# MXP_part.net
KiCad netlist of a schematic drawn in EAGLE
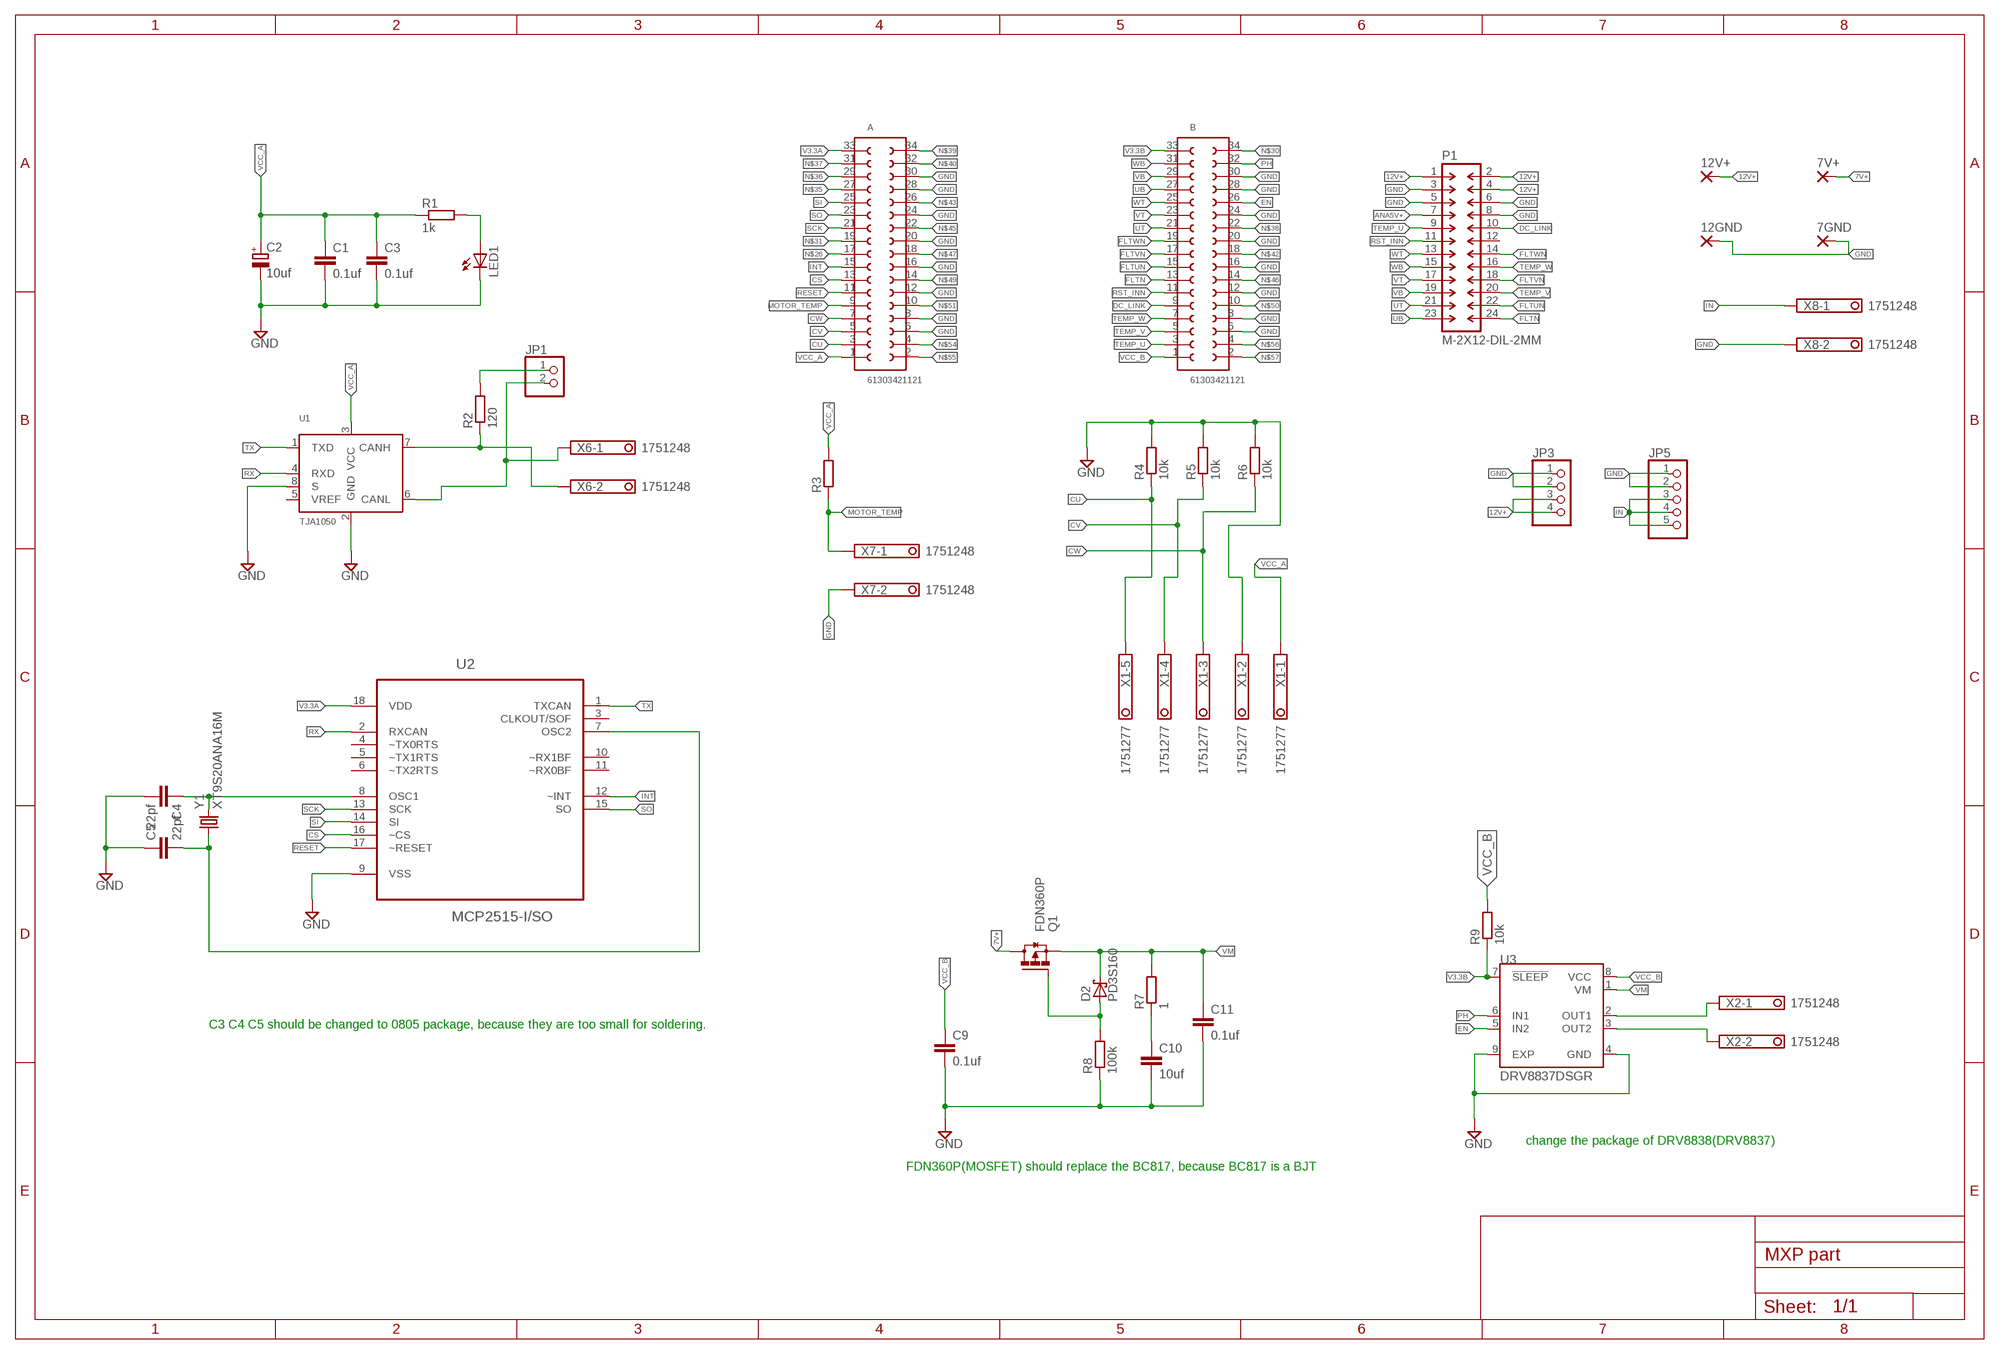
[diagram p0: schematic, sheet 1]

(export (version "E")
  (design (tool "Eeschema 10.0.6"))
  (components
    (comp (ref "7GND")
      (value "2,54/0,9")
      (footprint "eagle-import:2,54_0,9")
      (libsource (lib "eagle-import") (part "2,54/0,9"))
    )
    (comp (ref "7V+")
      (value "2,54/0,9")
      (footprint "eagle-import:2,54_0,9")
      (libsource (lib "eagle-import") (part "2,54/0,9"))
    )
    (comp (ref "12GND")
      (value "2,54/0,9")
      (footprint "eagle-import:2,54_0,9")
      (libsource (lib "eagle-import") (part "2,54/0,9"))
    )
    (comp (ref "12V+")
      (value "2,54/0,9")
      (footprint "eagle-import:2,54_0,9")
      (libsource (lib "eagle-import") (part "2,54/0,9"))
    )
    (comp (ref "A")
      (value "61303421121")
      (footprint "eagle-import:61303421121")
      (fields (field (name "MF") "Würth Elektronik"))
      (libsource (lib "eagle-import") (part "61303421121"))
    )
    (comp (ref "B")
      (value "61303421121")
      (footprint "eagle-import:61303421121")
      (fields (field (name "MF") "Würth Elektronik"))
      (libsource (lib "eagle-import") (part "61303421121"))
    )
    (comp (ref "C1")
      (value "0.1uf")
      (footprint "eagle-import:C0402K")
      (libsource (lib "eagle-import") (part "C-EUC0402K"))
    )
    (comp (ref "C2")
      (value "10uf")
      (footprint "eagle-import:A_3216-18W")
      (libsource (lib "eagle-import") (part "CPOL-EUA/3216-18W"))
    )
    (comp (ref "C3")
      (value "0.1uf")
      (footprint "eagle-import:C0402K")
      (libsource (lib "eagle-import") (part "C-EUC0402K"))
    )
    (comp (ref "C4")
      (value "22pf")
      (footprint "eagle-import:C0402K")
      (libsource (lib "eagle-import") (part "C-EUC0402K"))
    )
    (comp (ref "C5")
      (value "22pf")
      (footprint "eagle-import:C0402K")
      (libsource (lib "eagle-import") (part "C-EUC0402K"))
    )
    (comp (ref "C9")
      (value "0.1uf")
      (footprint "eagle-import:C0603K")
      (libsource (lib "eagle-import") (part "C-EUC0603K"))
    )
    (comp (ref "C10")
      (value "10uf")
      (footprint "eagle-import:C0603K")
      (libsource (lib "eagle-import") (part "C-EUC0603K"))
    )
    (comp (ref "C11")
      (value "0.1uf")
      (footprint "eagle-import:C0603K")
      (libsource (lib "eagle-import") (part "C-EUC0603K"))
    )
    (comp (ref "D2")
      (value "PD3S160")
      (footprint "eagle-import:POWERDI323")
      (libsource (lib "eagle-import") (part "PD3S160"))
    )
    (comp (ref "JP1")
      (value "PINHD-1X2")
      (footprint "eagle-import:1X02")
      (libsource (lib "eagle-import") (part "PINHD-1X2"))
    )
    (comp (ref "JP3")
      (value "PINHD-1X4")
      (footprint "eagle-import:1X04")
      (libsource (lib "eagle-import") (part "PINHD-1X4"))
    )
    (comp (ref "JP5")
      (value "PINHD-1X5")
      (footprint "eagle-import:1X05")
      (libsource (lib "eagle-import") (part "PINHD-1X5"))
    )
    (comp (ref "LED1")
      (value "LEDCHIP-LED0805")
      (footprint "eagle-import:CHIP-LED0805")
      (libsource (lib "eagle-import") (part "LEDCHIP-LED0805"))
    )
    (comp (ref "P1")
      (value "M-2X12-DIL-2MM")
      (footprint "eagle-import:DIL-2MM-2X12")
      (libsource (lib "eagle-import") (part "M-2X12-DIL-2MM"))
    )
    (comp (ref "Q1")
      (value "FDN360P")
      (footprint "eagle-import:SUPER-SOT3")
      (libsource (lib "eagle-import") (part "FDN360P"))
    )
    (comp (ref "R1")
      (value "1k")
      (footprint "eagle-import:R0603")
      (libsource (lib "eagle-import") (part "R-EU_R0603"))
    )
    (comp (ref "R2")
      (value "120")
      (footprint "eagle-import:R0603")
      (libsource (lib "eagle-import") (part "R-EU_R0603"))
    )
    (comp (ref "R3")
      (value "R-EU_0204/7")
      (footprint "eagle-import:0204_7")
      (libsource (lib "eagle-import") (part "R-EU_0204/7"))
    )
    (comp (ref "R4")
      (value "10k")
      (footprint "eagle-import:0204_7")
      (libsource (lib "eagle-import") (part "R-EU_0204/7"))
    )
    (comp (ref "R5")
      (value "10k")
      (footprint "eagle-import:0204_7")
      (libsource (lib "eagle-import") (part "R-EU_0204/7"))
    )
    (comp (ref "R6")
      (value "10k")
      (footprint "eagle-import:0204_7")
      (libsource (lib "eagle-import") (part "R-EU_0204/7"))
    )
    (comp (ref "R7")
      (value "1")
      (footprint "eagle-import:R0603")
      (libsource (lib "eagle-import") (part "R-EU_R0603"))
    )
    (comp (ref "R8")
      (value "100k")
      (footprint "eagle-import:R0603")
      (libsource (lib "eagle-import") (part "R-EU_R0603"))
    )
    (comp (ref "R9")
      (value "10k")
      (footprint "eagle-import:R0603")
      (libsource (lib "eagle-import") (part "R-EU_R0603"))
    )
    (comp (ref "U1")
      (value "TJA1050")
      (footprint "eagle-import:SOT96-1")
      (libsource (lib "eagle-import") (part "TJA1050"))
    )
    (comp (ref "U2")
      (value "MCP2515-I/SO")
      (footprint "eagle-import:SOIC127P1034X264-18N")
      (fields (field (name "MF") "Microchip"))
      (libsource (lib "eagle-import") (part "MCP2515-I/SO"))
    )
    (comp (ref "U3")
      (value "DRV8837DSGR")
      (footprint "eagle-import:SON50P200X200X80-9N")
      (fields (field (name "MF") "Texas Instruments"))
      (libsource (lib "eagle-import") (part "DRV8837DSGR"))
    )
    (comp (ref "X1")
      (value "1751277")
      (footprint "eagle-import:1751277")
      (libsource (lib "eagle-import") (part "1751277"))
    )
    (comp (ref "X2")
      (value "1751248")
      (footprint "eagle-import:1751248")
      (libsource (lib "eagle-import") (part "1751248"))
    )
    (comp (ref "X6")
      (value "1751248")
      (footprint "eagle-import:1751248")
      (libsource (lib "eagle-import") (part "1751248"))
    )
    (comp (ref "X7")
      (value "1751248")
      (footprint "eagle-import:1751248")
      (libsource (lib "eagle-import") (part "1751248"))
    )
    (comp (ref "X8")
      (value "1751248")
      (footprint "eagle-import:1751248")
      (libsource (lib "eagle-import") (part "1751248"))
    )
    (comp (ref "Y1")
      (value "XT9S20ANA16M")
      (footprint "eagle-import:XTAL_XT9S20ANA16M")
      (fields (field (name "MF") "Vishay Dale"))
      (libsource (lib "eagle-import") (part "XT9S20ANA16M"))
    )
  )
  (nets
    (net (code "1") (name "7V+") (class "Default")
      (node (ref "7V+") (pin "1") (pinfunction "P_1") (pintype "passive"))
      (node (ref "Q1") (pin "3") (pinfunction "D_3") (pintype "passive"))
    )
    (net (code "2") (name "12V+") (class "Default")
      (node (ref "12V+") (pin "1") (pinfunction "P_1") (pintype "passive"))
      (node (ref "JP3") (pin "3") (pinfunction "3_3") (pintype "passive"))
      (node (ref "JP3") (pin "4") (pinfunction "4_4") (pintype "passive"))
      (node (ref "P1") (pin "1") (pinfunction "1_1") (pintype "passive"))
      (node (ref "P1") (pin "2") (pinfunction "2_2") (pintype "passive"))
      (node (ref "P1") (pin "4") (pinfunction "4_4") (pintype "passive"))
    )
    (net (code "3") (name "ANA5V+") (class "Default")
      (node (ref "P1") (pin "7") (pinfunction "7_7") (pintype "passive"))
    )
    (net (code "4") (name "CS") (class "Default")
      (node (ref "A") (pin "13") (pinfunction "13_13") (pintype "passive"))
      (node (ref "U2") (pin "16") (pinfunction "~{CS}_16") (pintype "input"))
    )
    (net (code "5") (name "CU") (class "Default")
      (node (ref "A") (pin "3") (pinfunction "3_3") (pintype "passive"))
      (node (ref "R4") (pin "1") (pinfunction "1_1") (pintype "passive"))
      (node (ref "X1") (pin "5") (pinfunction "K_5") (pintype "passive"))
    )
    (net (code "6") (name "CV") (class "Default")
      (node (ref "A") (pin "5") (pinfunction "5_5") (pintype "passive"))
      (node (ref "R5") (pin "1") (pinfunction "1_1") (pintype "passive"))
      (node (ref "X1") (pin "4") (pinfunction "K_4") (pintype "passive"))
    )
    (net (code "7") (name "CW") (class "Default")
      (node (ref "A") (pin "7") (pinfunction "7_7") (pintype "passive"))
      (node (ref "R6") (pin "1") (pinfunction "1_1") (pintype "passive"))
      (node (ref "X1") (pin "3") (pinfunction "K_3") (pintype "passive"))
    )
    (net (code "8") (name "DC_LINK") (class "Default")
      (node (ref "B") (pin "9") (pinfunction "9_9") (pintype "passive"))
      (node (ref "P1") (pin "10") (pinfunction "10_10") (pintype "passive"))
    )
    (net (code "9") (name "EN") (class "Default")
      (node (ref "B") (pin "26") (pinfunction "26_26") (pintype "passive"))
      (node (ref "U3") (pin "5") (pinfunction "IN2_5") (pintype "input"))
    )
    (net (code "10") (name "FLTN") (class "Default")
      (node (ref "B") (pin "13") (pinfunction "13_13") (pintype "passive"))
      (node (ref "P1") (pin "24") (pinfunction "24_24") (pintype "passive"))
    )
    (net (code "11") (name "FLTUN") (class "Default")
      (node (ref "B") (pin "15") (pinfunction "15_15") (pintype "passive"))
      (node (ref "P1") (pin "22") (pinfunction "22_22") (pintype "passive"))
    )
    (net (code "12") (name "FLTVN") (class "Default")
      (node (ref "B") (pin "17") (pinfunction "17_17") (pintype "passive"))
      (node (ref "P1") (pin "18") (pinfunction "18_18") (pintype "passive"))
    )
    (net (code "13") (name "FLTWN") (class "Default")
      (node (ref "B") (pin "19") (pinfunction "19_19") (pintype "passive"))
      (node (ref "P1") (pin "14") (pinfunction "14_14") (pintype "passive"))
    )
    (net (code "14") (name "GND") (class "Default")
      (node (ref "12GND") (pin "1") (pinfunction "P_1") (pintype "passive"))
      (node (ref "7GND") (pin "1") (pinfunction "P_1") (pintype "passive"))
      (node (ref "A") (pin "12") (pinfunction "12_12") (pintype "passive"))
      (node (ref "A") (pin "16") (pinfunction "16_16") (pintype "passive"))
      (node (ref "A") (pin "20") (pinfunction "20_20") (pintype "passive"))
      (node (ref "A") (pin "24") (pinfunction "24_24") (pintype "passive"))
      (node (ref "A") (pin "28") (pinfunction "28_28") (pintype "passive"))
      (node (ref "A") (pin "30") (pinfunction "30_30") (pintype "passive"))
      (node (ref "A") (pin "6") (pinfunction "6_6") (pintype "passive"))
      (node (ref "A") (pin "8") (pinfunction "8_8") (pintype "passive"))
      (node (ref "B") (pin "12") (pinfunction "12_12") (pintype "passive"))
      (node (ref "B") (pin "16") (pinfunction "16_16") (pintype "passive"))
      (node (ref "B") (pin "20") (pinfunction "20_20") (pintype "passive"))
      (node (ref "B") (pin "24") (pinfunction "24_24") (pintype "passive"))
      (node (ref "B") (pin "28") (pinfunction "28_28") (pintype "passive"))
      (node (ref "B") (pin "30") (pinfunction "30_30") (pintype "passive"))
      (node (ref "B") (pin "6") (pinfunction "6_6") (pintype "passive"))
      (node (ref "B") (pin "8") (pinfunction "8_8") (pintype "passive"))
      (node (ref "C1") (pin "2") (pinfunction "2_2") (pintype "passive"))
      (node (ref "C10") (pin "2") (pinfunction "2_2") (pintype "passive"))
      (node (ref "C11") (pin "2") (pinfunction "2_2") (pintype "passive"))
      (node (ref "C2") (pin "-") (pinfunction "-_-") (pintype "passive"))
      (node (ref "C3") (pin "2") (pinfunction "2_2") (pintype "passive"))
      (node (ref "C4") (pin "2") (pinfunction "2_2") (pintype "passive"))
      (node (ref "C5") (pin "1") (pinfunction "1_1") (pintype "passive"))
      (node (ref "C9") (pin "2") (pinfunction "2_2") (pintype "passive"))
      (node (ref "JP3") (pin "1") (pinfunction "1_1") (pintype "passive"))
      (node (ref "JP3") (pin "2") (pinfunction "2_2") (pintype "passive"))
      (node (ref "JP5") (pin "1") (pinfunction "1_1") (pintype "passive"))
      (node (ref "JP5") (pin "2") (pinfunction "2_2") (pintype "passive"))
      (node (ref "LED1") (pin "C") (pinfunction "C_C") (pintype "passive"))
      (node (ref "P1") (pin "3") (pinfunction "3_3") (pintype "passive"))
      (node (ref "P1") (pin "5") (pinfunction "5_5") (pintype "passive"))
      (node (ref "P1") (pin "6") (pinfunction "6_6") (pintype "passive"))
      (node (ref "P1") (pin "8") (pinfunction "8_8") (pintype "passive"))
      (node (ref "R4") (pin "2") (pinfunction "2_2") (pintype "passive"))
      (node (ref "R5") (pin "2") (pinfunction "2_2") (pintype "passive"))
      (node (ref "R6") (pin "2") (pinfunction "2_2") (pintype "passive"))
      (node (ref "R8") (pin "1") (pinfunction "1_1") (pintype "passive"))
      (node (ref "U1") (pin "2") (pinfunction "GND_2") (pintype "bidirectional"))
      (node (ref "U1") (pin "8") (pinfunction "S_8") (pintype "power_in"))
      (node (ref "U2") (pin "9") (pinfunction "VSS_9") (pintype "power_in"))
      (node (ref "U3") (pin "4") (pinfunction "GND_4") (pintype "power_in"))
      (node (ref "U3") (pin "9") (pinfunction "EXP_9") (pintype "passive"))
      (node (ref "X1") (pin "2") (pinfunction "K_2") (pintype "passive"))
      (node (ref "X7") (pin "2") (pinfunction "K_2") (pintype "passive"))
      (node (ref "X8") (pin "2") (pinfunction "K_2") (pintype "passive"))
    )
    (net (code "15") (name "IN") (class "Default")
      (node (ref "JP5") (pin "3") (pinfunction "3_3") (pintype "passive"))
      (node (ref "JP5") (pin "4") (pinfunction "4_4") (pintype "passive"))
      (node (ref "JP5") (pin "5") (pinfunction "5_5") (pintype "passive"))
      (node (ref "X8") (pin "1") (pinfunction "K_1") (pintype "passive"))
    )
    (net (code "16") (name "INT") (class "Default")
      (node (ref "A") (pin "15") (pinfunction "15_15") (pintype "passive"))
      (node (ref "U2") (pin "12") (pinfunction "~{INT}_12") (pintype "output"))
    )
    (net (code "17") (name "MOTOR_TEMP") (class "Default")
      (node (ref "A") (pin "9") (pinfunction "9_9") (pintype "passive"))
      (node (ref "R3") (pin "1") (pinfunction "1_1") (pintype "passive"))
      (node (ref "X7") (pin "1") (pinfunction "K_1") (pintype "passive"))
    )
    (net (code "18") (name "N$26") (class "Default")
      (node (ref "A") (pin "17") (pinfunction "17_17") (pintype "passive"))
    )
    (net (code "19") (name "N$30") (class "Default")
      (node (ref "B") (pin "34") (pinfunction "34_34") (pintype "passive"))
    )
    (net (code "20") (name "N$31") (class "Default")
      (node (ref "A") (pin "19") (pinfunction "19_19") (pintype "passive"))
    )
    (net (code "21") (name "N$35") (class "Default")
      (node (ref "A") (pin "27") (pinfunction "27_27") (pintype "passive"))
    )
    (net (code "22") (name "N$36") (class "Default")
      (node (ref "A") (pin "29") (pinfunction "29_29") (pintype "passive"))
    )
    (net (code "23") (name "N$37") (class "Default")
      (node (ref "A") (pin "31") (pinfunction "31_31") (pintype "passive"))
    )
    (net (code "24") (name "N$38") (class "Default")
      (node (ref "B") (pin "22") (pinfunction "22_22") (pintype "passive"))
    )
    (net (code "25") (name "N$39") (class "Default")
      (node (ref "A") (pin "34") (pinfunction "34_34") (pintype "passive"))
    )
    (net (code "26") (name "N$40") (class "Default")
      (node (ref "A") (pin "32") (pinfunction "32_32") (pintype "passive"))
    )
    (net (code "27") (name "N$42") (class "Default")
      (node (ref "B") (pin "18") (pinfunction "18_18") (pintype "passive"))
    )
    (net (code "28") (name "N$43") (class "Default")
      (node (ref "A") (pin "26") (pinfunction "26_26") (pintype "passive"))
    )
    (net (code "29") (name "N$45") (class "Default")
      (node (ref "A") (pin "22") (pinfunction "22_22") (pintype "passive"))
    )
    (net (code "30") (name "N$46") (class "Default")
      (node (ref "B") (pin "14") (pinfunction "14_14") (pintype "passive"))
    )
    (net (code "31") (name "N$47") (class "Default")
      (node (ref "A") (pin "18") (pinfunction "18_18") (pintype "passive"))
    )
    (net (code "32") (name "N$49") (class "Default")
      (node (ref "A") (pin "14") (pinfunction "14_14") (pintype "passive"))
    )
    (net (code "33") (name "N$50") (class "Default")
      (node (ref "B") (pin "10") (pinfunction "10_10") (pintype "passive"))
    )
    (net (code "34") (name "N$51") (class "Default")
      (node (ref "A") (pin "10") (pinfunction "10_10") (pintype "passive"))
    )
    (net (code "35") (name "N$54") (class "Default")
      (node (ref "A") (pin "4") (pinfunction "4_4") (pintype "passive"))
    )
    (net (code "36") (name "N$55") (class "Default")
      (node (ref "A") (pin "2") (pinfunction "2_2") (pintype "passive"))
    )
    (net (code "37") (name "N$56") (class "Default")
      (node (ref "B") (pin "4") (pinfunction "4_4") (pintype "passive"))
    )
    (net (code "38") (name "N$57") (class "Default")
      (node (ref "B") (pin "2") (pinfunction "2_2") (pintype "passive"))
    )
    (net (code "39") (name "Net-(C10-Pad1)") (class "Default")
      (node (ref "C10") (pin "1") (pinfunction "1_1") (pintype "passive"))
      (node (ref "R7") (pin "1") (pinfunction "1_1") (pintype "passive"))
    )
    (net (code "40") (name "Net-(JP1-Pad1)") (class "Default")
      (node (ref "JP1") (pin "1") (pinfunction "1_1") (pintype "passive"))
      (node (ref "R2") (pin "2") (pinfunction "2_2") (pintype "passive"))
    )
    (net (code "41") (name "Net-(LED1-PadA)") (class "Default")
      (node (ref "LED1") (pin "A") (pinfunction "A_A") (pintype "passive"))
      (node (ref "R1") (pin "2") (pinfunction "2_2") (pintype "passive"))
    )
    (net (code "42") (name "Net-(Q1-G)") (class "Default")
      (node (ref "D2") (pin "A") (pinfunction "A_A") (pintype "passive"))
      (node (ref "Q1") (pin "1") (pinfunction "G_1") (pintype "passive"))
      (node (ref "R8") (pin "2") (pinfunction "2_2") (pintype "passive"))
    )
    (net (code "43") (name "Net-(U1-CANH)") (class "Default")
      (node (ref "R2") (pin "1") (pinfunction "1_1") (pintype "passive"))
      (node (ref "U1") (pin "7") (pinfunction "CANH_7") (pintype "bidirectional"))
      (node (ref "X6") (pin "2") (pinfunction "K_2") (pintype "passive"))
    )
    (net (code "44") (name "Net-(U1-CANL)") (class "Default")
      (node (ref "JP1") (pin "2") (pinfunction "2_2") (pintype "passive"))
      (node (ref "U1") (pin "6") (pinfunction "CANL_6") (pintype "bidirectional"))
      (node (ref "X6") (pin "1") (pinfunction "K_1") (pintype "passive"))
    )
    (net (code "45") (name "Net-(U2-OSC1)") (class "Default")
      (node (ref "C4") (pin "1") (pinfunction "1_1") (pintype "passive"))
      (node (ref "U2") (pin "8") (pinfunction "OSC1_8") (pintype "input"))
      (node (ref "Y1") (pin "2") (pinfunction "2_2") (pintype "passive"))
    )
    (net (code "46") (name "Net-(U2-OSC2)") (class "Default")
      (node (ref "C5") (pin "2") (pinfunction "2_2") (pintype "passive"))
      (node (ref "U2") (pin "7") (pinfunction "OSC2_7") (pintype "output"))
      (node (ref "Y1") (pin "1") (pinfunction "1_1") (pintype "passive"))
    )
    (net (code "47") (name "Net-(U3-OUT1)") (class "Default")
      (node (ref "U3") (pin "2") (pinfunction "OUT1_2") (pintype "output"))
      (node (ref "X2") (pin "1") (pinfunction "K_1") (pintype "passive"))
    )
    (net (code "48") (name "Net-(U3-OUT2)") (class "Default")
      (node (ref "U3") (pin "3") (pinfunction "OUT2_3") (pintype "output"))
      (node (ref "X2") (pin "2") (pinfunction "K_2") (pintype "passive"))
    )
    (net (code "49") (name "PH") (class "Default")
      (node (ref "B") (pin "32") (pinfunction "32_32") (pintype "passive"))
      (node (ref "U3") (pin "6") (pinfunction "IN1_6") (pintype "input"))
    )
    (net (code "50") (name "RESET") (class "Default")
      (node (ref "A") (pin "11") (pinfunction "11_11") (pintype "passive"))
      (node (ref "U2") (pin "17") (pinfunction "~{RESET}_17") (pintype "input"))
    )
    (net (code "51") (name "RST_INN") (class "Default")
      (node (ref "B") (pin "11") (pinfunction "11_11") (pintype "passive"))
      (node (ref "P1") (pin "11") (pinfunction "11_11") (pintype "passive"))
    )
    (net (code "52") (name "RX") (class "Default")
      (node (ref "U1") (pin "4") (pinfunction "RXD_4") (pintype "bidirectional"))
      (node (ref "U2") (pin "2") (pinfunction "RXCAN_2") (pintype "input"))
    )
    (net (code "53") (name "SCK") (class "Default")
      (node (ref "A") (pin "21") (pinfunction "21_21") (pintype "passive"))
      (node (ref "U2") (pin "13") (pinfunction "SCK_13") (pintype "input"))
    )
    (net (code "54") (name "SI") (class "Default")
      (node (ref "A") (pin "25") (pinfunction "25_25") (pintype "passive"))
      (node (ref "U2") (pin "14") (pinfunction "SI_14") (pintype "input"))
    )
    (net (code "55") (name "SO") (class "Default")
      (node (ref "A") (pin "23") (pinfunction "23_23") (pintype "passive"))
      (node (ref "U2") (pin "15") (pinfunction "SO_15") (pintype "output"))
    )
    (net (code "56") (name "TEMP_U") (class "Default")
      (node (ref "B") (pin "3") (pinfunction "3_3") (pintype "passive"))
      (node (ref "P1") (pin "9") (pinfunction "9_9") (pintype "passive"))
    )
    (net (code "57") (name "TEMP_V") (class "Default")
      (node (ref "B") (pin "5") (pinfunction "5_5") (pintype "passive"))
      (node (ref "P1") (pin "20") (pinfunction "20_20") (pintype "passive"))
    )
    (net (code "58") (name "TEMP_W") (class "Default")
      (node (ref "B") (pin "7") (pinfunction "7_7") (pintype "passive"))
      (node (ref "P1") (pin "16") (pinfunction "16_16") (pintype "passive"))
    )
    (net (code "59") (name "TX") (class "Default")
      (node (ref "U1") (pin "1") (pinfunction "TXD_1") (pintype "output"))
      (node (ref "U2") (pin "1") (pinfunction "TXCAN_1") (pintype "output"))
    )
    (net (code "60") (name "UB") (class "Default")
      (node (ref "B") (pin "27") (pinfunction "27_27") (pintype "passive"))
      (node (ref "P1") (pin "23") (pinfunction "23_23") (pintype "passive"))
    )
    (net (code "61") (name "UT") (class "Default")
      (node (ref "B") (pin "21") (pinfunction "21_21") (pintype "passive"))
      (node (ref "P1") (pin "21") (pinfunction "21_21") (pintype "passive"))
    )
    (net (code "62") (name "V3.3A") (class "Default")
      (node (ref "A") (pin "33") (pinfunction "33_33") (pintype "passive"))
      (node (ref "U2") (pin "18") (pinfunction "VDD_18") (pintype "power_in"))
    )
    (net (code "63") (name "V3.3B") (class "Default")
      (node (ref "B") (pin "33") (pinfunction "33_33") (pintype "passive"))
      (node (ref "R9") (pin "1") (pinfunction "1_1") (pintype "passive"))
      (node (ref "U3") (pin "7") (pinfunction "~{SLEEP}_7") (pintype "input"))
    )
    (net (code "64") (name "VB") (class "Default")
      (node (ref "B") (pin "29") (pinfunction "29_29") (pintype "passive"))
      (node (ref "P1") (pin "19") (pinfunction "19_19") (pintype "passive"))
    )
    (net (code "65") (name "VCC_A") (class "Default")
      (node (ref "A") (pin "1") (pinfunction "1_1") (pintype "passive"))
      (node (ref "C1") (pin "1") (pinfunction "1_1") (pintype "passive"))
      (node (ref "C2") (pin "+") (pinfunction "+_+") (pintype "passive"))
      (node (ref "C3") (pin "1") (pinfunction "1_1") (pintype "passive"))
      (node (ref "R1") (pin "1") (pinfunction "1_1") (pintype "passive"))
      (node (ref "R3") (pin "2") (pinfunction "2_2") (pintype "passive"))
      (node (ref "U1") (pin "3") (pinfunction "VCC_3") (pintype "bidirectional"))
      (node (ref "X1") (pin "1") (pinfunction "K_1") (pintype "passive"))
    )
    (net (code "66") (name "VCC_B") (class "Default")
      (node (ref "B") (pin "1") (pinfunction "1_1") (pintype "passive"))
      (node (ref "C9") (pin "1") (pinfunction "1_1") (pintype "passive"))
      (node (ref "R9") (pin "2") (pinfunction "2_2") (pintype "passive"))
      (node (ref "U3") (pin "8") (pinfunction "VCC_8") (pintype "power_in"))
    )
    (net (code "67") (name "VM") (class "Default")
      (node (ref "C11") (pin "1") (pinfunction "1_1") (pintype "passive"))
      (node (ref "D2") (pin "C") (pinfunction "C_C") (pintype "passive"))
      (node (ref "Q1") (pin "2") (pinfunction "S_2") (pintype "passive"))
      (node (ref "R7") (pin "2") (pinfunction "2_2") (pintype "passive"))
      (node (ref "U3") (pin "1") (pinfunction "VM_1") (pintype "power_in"))
    )
    (net (code "68") (name "VT") (class "Default")
      (node (ref "B") (pin "23") (pinfunction "23_23") (pintype "passive"))
      (node (ref "P1") (pin "17") (pinfunction "17_17") (pintype "passive"))
    )
    (net (code "69") (name "WB") (class "Default")
      (node (ref "B") (pin "31") (pinfunction "31_31") (pintype "passive"))
      (node (ref "P1") (pin "15") (pinfunction "15_15") (pintype "passive"))
    )
    (net (code "70") (name "WT") (class "Default")
      (node (ref "B") (pin "25") (pinfunction "25_25") (pintype "passive"))
      (node (ref "P1") (pin "13") (pinfunction "13_13") (pintype "passive"))
    )
    (net (code "71") (name "unconnected-(P1-Pad12)") (class "Default")
      (node (ref "P1") (pin "12") (pinfunction "12_12") (pintype "passive"))
    )
    (net (code "72") (name "unconnected-(U1-VREF-Pad5)") (class "Default")
      (node (ref "U1") (pin "5") (pinfunction "VREF_5") (pintype "passive"))
    )
    (net (code "73") (name "unconnected-(U2-CLKOUT{slash}SOF-Pad3)") (class "Default")
      (node (ref "U2") (pin "3") (pinfunction "CLKOUT/SOF_3") (pintype "output"))
    )
    (net (code "74") (name "unconnected-(U2-~{RX0BF}-Pad11)") (class "Default")
      (node (ref "U2") (pin "11") (pinfunction "~{RX0BF}_11") (pintype "output"))
    )
    (net (code "75") (name "unconnected-(U2-~{RX1BF}-Pad10)") (class "Default")
      (node (ref "U2") (pin "10") (pinfunction "~{RX1BF}_10") (pintype "output"))
    )
    (net (code "76") (name "unconnected-(U2-~{TX0RTS}-Pad4)") (class "Default")
      (node (ref "U2") (pin "4") (pinfunction "~{TX0RTS}_4") (pintype "input"))
    )
    (net (code "77") (name "unconnected-(U2-~{TX1RTS}-Pad5)") (class "Default")
      (node (ref "U2") (pin "5") (pinfunction "~{TX1RTS}_5") (pintype "input"))
    )
    (net (code "78") (name "unconnected-(U2-~{TX2RTS}-Pad6)") (class "Default")
      (node (ref "U2") (pin "6") (pinfunction "~{TX2RTS}_6") (pintype "input"))
    )
  )
)
